# main.net
KiCad netlist of a schematic drawn in Altium Designer
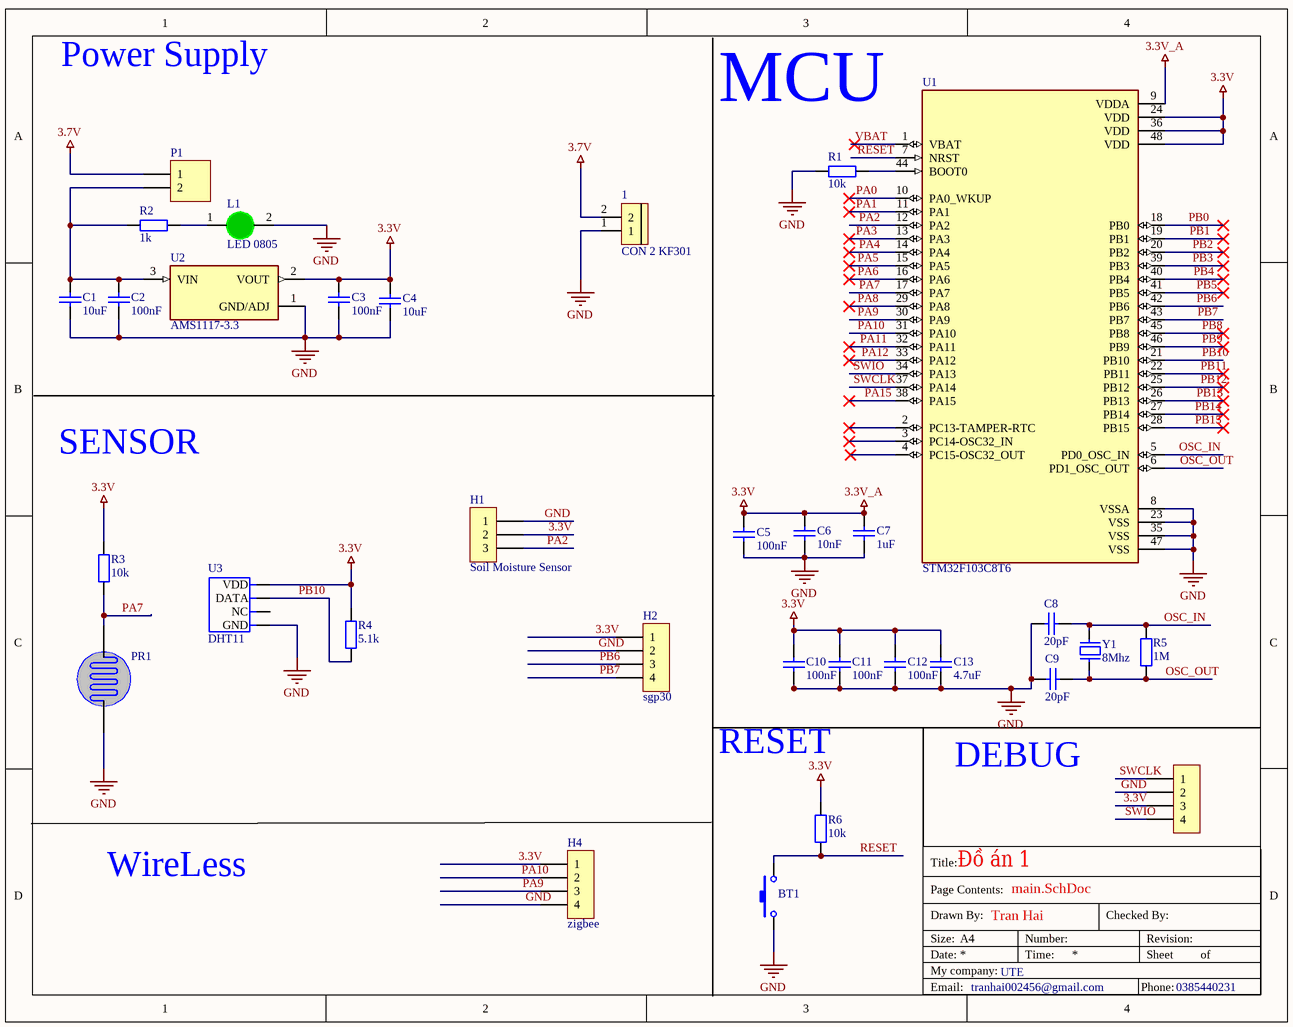
[diagram p0: main.SchDoc]

(export (version "E")
  (design (tool "Eeschema 10.0.6"))
  (components
    (comp (ref "1")
      (value "CON 2 KF301")
      (footprint "Con 2 KF301 5.08")
      (description "Cắm")
      (libsource (lib "Altium_Lib_by_KhueNguyenCreator") (part "CON 2 KF301"))
    )
    (comp (ref "BT1")
      (value "Nut Nhan 2 Chan SMD 3x6x2.5")
      (footprint "Nut Nhan 2 Chan SMD 3x6x2.5")
      (libsource (lib "Altium_Lib_by_KhueNguyenCreator") (part "Nut Nhan 2 Chan SMD 3x6x2.5"))
    )
    (comp (ref "C1")
      (value "10uF")
      (footprint "Tu 0805")
      (description "Dán")
      (libsource (lib "Altium_Lib_by_KhueNguyenCreator") (part "Tu 0805 200pF 50V 10%"))
    )
    (comp (ref "C2")
      (value "100nF")
      (footprint "Tu 0805")
      (description "Dán")
      (libsource (lib "Altium_Lib_by_KhueNguyenCreator") (part "Tu 0805 200pF 50V 10%"))
    )
    (comp (ref "C3")
      (value "100nF")
      (footprint "Tu 0805")
      (description "Dán")
      (libsource (lib "Altium_Lib_by_KhueNguyenCreator") (part "Tu 0805 200pF 50V 10%"))
    )
    (comp (ref "C4")
      (value "10uF")
      (footprint "Tu 0805")
      (description "Dán")
      (libsource (lib "Altium_Lib_by_KhueNguyenCreator") (part "Tu 0805 200pF 50V 10%"))
    )
    (comp (ref "C5")
      (value "100nF")
      (footprint "tu 0805")
      (description "Dán")
      (libsource (lib "") (part "Tu 0805 101 50V 20%_1"))
    )
    (comp (ref "C6")
      (value "10nF")
      (footprint "tu 0805")
      (description "Dán")
      (libsource (lib "") (part "Tu 0805 101 50V 20%_1"))
    )
    (comp (ref "C7")
      (value "1uF")
      (footprint "tu 0805")
      (description "Dán")
      (libsource (lib "") (part "Tu 0805 101 50V 20%_1"))
    )
    (comp (ref "C8")
      (value "20pF")
      (footprint "tu 0805")
      (description "Dán")
      (libsource (lib "") (part "Tu 0805 101 50V 20%_1"))
    )
    (comp (ref "C9")
      (value "20pF")
      (footprint "tu 0805")
      (description "Dán")
      (libsource (lib "") (part "Tu 0805 101 50V 20%_1"))
    )
    (comp (ref "C10")
      (value "100nF")
      (footprint "tu 0805")
      (description "Dán")
      (libsource (lib "Altium_Lib_by_KhueNguyenCreator") (part "Tu 0805 101 50V 20%"))
    )
    (comp (ref "C11")
      (value "100nF")
      (footprint "tu 0805")
      (description "Dán")
      (libsource (lib "Altium_Lib_by_KhueNguyenCreator") (part "Tu 0805 101 50V 20%"))
    )
    (comp (ref "C12")
      (value "100nF")
      (footprint "tu 0805")
      (description "Dán")
      (libsource (lib "Altium_Lib_by_KhueNguyenCreator") (part "Tu 0805 101 50V 20%"))
    )
    (comp (ref "C13")
      (value "4.7uF")
      (footprint "tu 0805")
      (description "Dán")
      (libsource (lib "Altium_Lib_by_KhueNguyenCreator") (part "Tu 0805 101 50V 20%"))
    )
    (comp (ref "H1")
      (value "Soil Moisture Sensor")
      (footprint "XH2.54M-3")
      (description "Cắm")
      (libsource (lib "Altium_Lib_by_KhueNguyenCreator") (part "Header 3P 2.54 Duc Thang"))
    )
    (comp (ref "H2")
      (value "sgp30")
      (footprint "XH2.54M-4")
      (description "Cắm")
      (libsource (lib "Altium_Lib_by_KhueNguyenCreator") (part "Header 4P 2.54 Duc Thang"))
    )
    (comp (ref "H3")
      (value "Header 4P 2.54 Duc Thang")
      (footprint "XH2.54M-4")
      (description "Cắm")
      (libsource (lib "Altium_Lib_by_KhueNguyenCreator") (part "Header 4P 2.54 Duc Thang"))
    )
    (comp (ref "H4")
      (value "zigbee")
      (footprint "XH2.54M-4")
      (description "Cắm")
      (libsource (lib "Altium_Lib_by_KhueNguyenCreator") (part "Header 4P 2.54 Duc Thang"))
    )
    (comp (ref "L1")
      (value "LED 0805")
      (footprint "LED-0805-Green")
      (description "Dán")
      (libsource (lib "Altium_Lib_by_KhueNguyenCreator") (part "LED 0805 Xanh La"))
    )
    (comp (ref "P1")
      (value "Header 2")
      (footprint "HDR1X2")
      (description "Header, 2-Pin")
      (fields (field (name "PUBLISHER") "Altium Limited"))
      (libsource (lib "Library AL") (part "Header 2"))
    )
    (comp (ref "PR1")
      (value "Quang Tro")
      (footprint "Quang Tro")
      (description "Photoresistor")
      (fields (field (name "CREATOR") "Bien Nguyen"))
      (libsource (lib "Altium_Lib_by_KhueNguyenCreator") (part "Quang Tro"))
    )
    (comp (ref "R1")
      (value "10k")
      (footprint "tro smd 0805")
      (description "Dán")
      (libsource (lib "Altium_Lib_by_KhueNguyenCreator") (part "Tro 0805 1% 10k"))
    )
    (comp (ref "R2")
      (value "1k")
      (footprint "tro smd 0805")
      (description "Dán")
      (libsource (lib "Altium_Lib_by_KhueNguyenCreator") (part "Tro 0805 1% 10k"))
    )
    (comp (ref "R3")
      (value "10k")
      (footprint "tro smd 0805")
      (description "Dán")
      (libsource (lib "Altium_Lib_by_KhueNguyenCreator") (part "Tro 0805 1% 10k"))
    )
    (comp (ref "R4")
      (value "5.1k")
      (footprint "tro smd 0805")
      (description "Dán")
      (libsource (lib "Altium_Lib_by_KhueNguyenCreator") (part "Tro 0805 1% 10k"))
    )
    (comp (ref "R5")
      (value "1M")
      (footprint "tro smd 0805")
      (description "Dán")
      (libsource (lib "Altium_Lib_by_KhueNguyenCreator") (part "Tro 0805 1% 10k"))
    )
    (comp (ref "R6")
      (value "10k")
      (footprint "tro smd 0805")
      (description "Dán")
      (libsource (lib "Altium_Lib_by_KhueNguyenCreator") (part "Tro 0805 1% 10k"))
    )
    (comp (ref "U1")
      (value "STM32F103C8T6")
      (footprint "QFP50P900X900X160-48N")
      (description "ARM® Cortex®-M3 STM32F1 Microcontroller IC 32-Bit 72MHz 64KB (64K x 8) FLASH 48-LQFP (7x7)")
      (fields (field (name "MF") "STMicroelectronics"))
      (libsource (lib "STM32F103C8T6") (part "STM32F103C8T6"))
    )
    (comp (ref "U2")
      (value "AMS1117-3.3")
      (footprint "SOT229P700X180-4N")
      (description "Sot223/Pkg 1-Amp 3.3-Volt Low Drop Out Voltage Regulatator")
      (fields (field (name "MF") "Advanced Monolithic Systems"))
      (libsource (lib "AMS1117-3.3") (part "AMS1117-3.3"))
    )
    (comp (ref "U3")
      (value "DHT11")
      (footprint "SNR4-2.54-15.5X12.0X5.5MM")
      (description "Äá»™ áº©m, nhiá»‡t Ä‘á»™ Ká»¹ thuáº­t sá»‘ Â±5% RH qua lá»—")
      (fields (field (name "MF") "UNIVERSAL-SOLDER Electronics Ltd"))
      (libsource (lib "TEM-HUM-DHT11_4P-15.5X12.0MM_") (part "TEM-HUM-DHT11(4P-15.5X12.0MM)"))
    )
    (comp (ref "Y1")
      (value "8Mhz")
      (footprint "Thach Anh 2 chan cam")
      (description "Crystal For all Crystal 2pin.")
      (libsource (lib "Altium_Lib_by_KhueNguyenCreator") (part "Thach Anh 2 chan Cam"))
    )
  )
  (nets
    (net (code "1") (name "/OSC_IN") (class "Default")
      (node (ref "C8") (pin "1") (pinfunction "1_1") (pintype "passive"))
      (node (ref "R5") (pin "2") (pinfunction "2_2") (pintype "passive"))
      (node (ref "U1") (pin "5") (pinfunction "PD0_OSC_IN_5") (pintype "bidirectional"))
      (node (ref "Y1") (pin "2") (pinfunction "2_2") (pintype "passive"))
    )
    (net (code "2") (name "/OSC_OUT") (class "Default")
      (node (ref "C9") (pin "1") (pinfunction "1_1") (pintype "passive"))
      (node (ref "R5") (pin "1") (pinfunction "1_1") (pintype "passive"))
      (node (ref "U1") (pin "6") (pinfunction "PD1_OSC_OUT_6") (pintype "bidirectional"))
      (node (ref "Y1") (pin "1") (pinfunction "1_1") (pintype "passive"))
    )
    (net (code "3") (name "/PA0") (class "Default")
      (node (ref "U1") (pin "10") (pinfunction "PA0_WKUP_10") (pintype "bidirectional+no_connect"))
    )
    (net (code "4") (name "/PA1") (class "Default")
      (node (ref "U1") (pin "11") (pinfunction "PA1_11") (pintype "bidirectional+no_connect"))
    )
    (net (code "5") (name "/PA2") (class "Default")
      (node (ref "H1") (pin "3") (pinfunction "3_3") (pintype "passive"))
      (node (ref "U1") (pin "12") (pinfunction "PA2_12") (pintype "bidirectional"))
    )
    (net (code "6") (name "/PA3") (class "Default")
      (node (ref "U1") (pin "13") (pinfunction "PA3_13") (pintype "bidirectional+no_connect"))
    )
    (net (code "7") (name "/PA4") (class "Default")
      (node (ref "U1") (pin "14") (pinfunction "PA4_14") (pintype "bidirectional+no_connect"))
    )
    (net (code "8") (name "/PA5") (class "Default")
      (node (ref "U1") (pin "15") (pinfunction "PA5_15") (pintype "bidirectional+no_connect"))
    )
    (net (code "9") (name "/PA6") (class "Default")
      (node (ref "U1") (pin "16") (pinfunction "PA6_16") (pintype "bidirectional+no_connect"))
    )
    (net (code "10") (name "/PA7") (class "Default")
      (node (ref "PR1") (pin "1") (pinfunction "1_1") (pintype "passive"))
      (node (ref "R3") (pin "1") (pinfunction "1_1") (pintype "passive"))
      (node (ref "U1") (pin "17") (pinfunction "PA7_17") (pintype "bidirectional"))
    )
    (net (code "11") (name "/PA8") (class "Default")
      (node (ref "U1") (pin "29") (pinfunction "PA8_29") (pintype "bidirectional+no_connect"))
    )
    (net (code "12") (name "/PA9") (class "Default")
      (node (ref "H4") (pin "3") (pinfunction "3_3") (pintype "passive"))
      (node (ref "U1") (pin "30") (pinfunction "PA9_30") (pintype "bidirectional"))
    )
    (net (code "13") (name "/PA10") (class "Default")
      (node (ref "H4") (pin "2") (pinfunction "2_2") (pintype "passive"))
      (node (ref "U1") (pin "31") (pinfunction "PA10_31") (pintype "bidirectional"))
    )
    (net (code "14") (name "/PA11") (class "Default")
      (node (ref "U1") (pin "32") (pinfunction "PA11_32") (pintype "bidirectional+no_connect"))
    )
    (net (code "15") (name "/PA12") (class "Default")
      (node (ref "U1") (pin "33") (pinfunction "PA12_33") (pintype "bidirectional+no_connect"))
    )
    (net (code "16") (name "/PA15") (class "Default")
      (node (ref "U1") (pin "38") (pinfunction "PA15_38") (pintype "bidirectional+no_connect"))
    )
    (net (code "17") (name "/PB0") (class "Default")
      (node (ref "U1") (pin "18") (pinfunction "PB0_18") (pintype "bidirectional+no_connect"))
    )
    (net (code "18") (name "/PB1") (class "Default")
      (node (ref "U1") (pin "19") (pinfunction "PB1_19") (pintype "bidirectional+no_connect"))
    )
    (net (code "19") (name "/PB2") (class "Default")
      (node (ref "U1") (pin "20") (pinfunction "PB2_20") (pintype "bidirectional+no_connect"))
    )
    (net (code "20") (name "/PB3") (class "Default")
      (node (ref "U1") (pin "39") (pinfunction "PB3_39") (pintype "bidirectional+no_connect"))
    )
    (net (code "21") (name "/PB4") (class "Default")
      (node (ref "U1") (pin "40") (pinfunction "PB4_40") (pintype "bidirectional+no_connect"))
    )
    (net (code "22") (name "/PB5") (class "Default")
      (node (ref "U1") (pin "41") (pinfunction "PB5_41") (pintype "bidirectional+no_connect"))
    )
    (net (code "23") (name "/PB6") (class "Default")
      (node (ref "H2") (pin "3") (pinfunction "3_3") (pintype "passive"))
      (node (ref "U1") (pin "42") (pinfunction "PB6_42") (pintype "bidirectional"))
    )
    (net (code "24") (name "/PB7") (class "Default")
      (node (ref "H2") (pin "4") (pinfunction "4_4") (pintype "passive"))
      (node (ref "U1") (pin "43") (pinfunction "PB7_43") (pintype "bidirectional"))
    )
    (net (code "25") (name "/PB8") (class "Default")
      (node (ref "U1") (pin "45") (pinfunction "PB8_45") (pintype "bidirectional+no_connect"))
    )
    (net (code "26") (name "/PB9") (class "Default")
      (node (ref "U1") (pin "46") (pinfunction "PB9_46") (pintype "bidirectional+no_connect"))
    )
    (net (code "27") (name "/PB10") (class "Default")
      (node (ref "R4") (pin "1") (pinfunction "1_1") (pintype "passive"))
      (node (ref "U1") (pin "21") (pinfunction "PB10_21") (pintype "bidirectional"))
      (node (ref "U3") (pin "2") (pinfunction "DATA_2") (pintype "bidirectional"))
    )
    (net (code "28") (name "/PB11") (class "Default")
      (node (ref "U1") (pin "22") (pinfunction "PB11_22") (pintype "bidirectional+no_connect"))
    )
    (net (code "29") (name "/PB12") (class "Default")
      (node (ref "U1") (pin "25") (pinfunction "PB12_25") (pintype "bidirectional+no_connect"))
    )
    (net (code "30") (name "/PB13") (class "Default")
      (node (ref "U1") (pin "26") (pinfunction "PB13_26") (pintype "bidirectional+no_connect"))
    )
    (net (code "31") (name "/PB14") (class "Default")
      (node (ref "U1") (pin "27") (pinfunction "PB14_27") (pintype "bidirectional+no_connect"))
    )
    (net (code "32") (name "/PB15") (class "Default")
      (node (ref "U1") (pin "28") (pinfunction "PB15_28") (pintype "bidirectional+no_connect"))
    )
    (net (code "33") (name "/RESET") (class "Default")
      (node (ref "BT1") (pin "2") (pinfunction "2_2") (pintype "passive"))
      (node (ref "R6") (pin "1") (pinfunction "1_1") (pintype "passive"))
      (node (ref "U1") (pin "7") (pinfunction "NRST_7") (pintype "input"))
    )
    (net (code "34") (name "/SWCLK") (class "Default")
      (node (ref "H3") (pin "1") (pinfunction "1_1") (pintype "passive"))
      (node (ref "U1") (pin "37") (pinfunction "PA14_37") (pintype "bidirectional"))
    )
    (net (code "35") (name "/SWIO") (class "Default")
      (node (ref "H3") (pin "4") (pinfunction "4_4") (pintype "passive"))
      (node (ref "U1") (pin "34") (pinfunction "PA13_34") (pintype "bidirectional"))
    )
    (net (code "37") (name "/VBAT") (class "Default")
      (node (ref "U1") (pin "1") (pinfunction "VBAT_1") (pintype "bidirectional"))
    )
    (net (code "38") (name "3.3V") (class "Default")
      (node (ref "C10") (pin "1") (pinfunction "1_1") (pintype "passive"))
      (node (ref "C11") (pin "1") (pinfunction "1_1") (pintype "passive"))
      (node (ref "C12") (pin "1") (pinfunction "1_1") (pintype "passive"))
      (node (ref "C13") (pin "1") (pinfunction "1_1") (pintype "passive"))
      (node (ref "C3") (pin "1") (pinfunction "1_1") (pintype "passive"))
      (node (ref "C4") (pin "1") (pinfunction "1_1") (pintype "passive"))
      (node (ref "C5") (pin "1") (pinfunction "1_1") (pintype "passive"))
      (node (ref "C6") (pin "1") (pinfunction "1_1") (pintype "passive"))
      (node (ref "C7") (pin "1") (pinfunction "1_1") (pintype "passive"))
      (node (ref "H1") (pin "2") (pinfunction "2_2") (pintype "passive"))
      (node (ref "H2") (pin "1") (pinfunction "1_1") (pintype "passive"))
      (node (ref "H3") (pin "3") (pinfunction "3_3") (pintype "passive"))
      (node (ref "H4") (pin "1") (pinfunction "1_1") (pintype "passive"))
      (node (ref "R3") (pin "2") (pinfunction "2_2") (pintype "passive"))
      (node (ref "R4") (pin "2") (pinfunction "2_2") (pintype "passive"))
      (node (ref "R6") (pin "2") (pinfunction "2_2") (pintype "passive"))
      (node (ref "U1") (pin "24") (pinfunction "VDD_24") (pintype "power_in"))
      (node (ref "U1") (pin "36") (pinfunction "VDD_36") (pintype "power_in"))
      (node (ref "U1") (pin "48") (pinfunction "VDD_48") (pintype "power_in"))
      (node (ref "U1") (pin "9") (pinfunction "VDDA_9") (pintype "power_in"))
      (node (ref "U2") (pin "2") (pinfunction "VOUT_2") (pintype "output"))
      (node (ref "U3") (pin "1") (pinfunction "VDD_1") (pintype "power_in"))
    )
    (net (code "39") (name "3.7V") (class "Default")
      (node (ref "1") (pin "2") (pinfunction "2_2") (pintype "passive"))
      (node (ref "P1") (pin "1") (pinfunction "1_1") (pintype "passive"))
    )
    (net (code "40") (name "GND") (class "Default")
      (node (ref "1") (pin "1") (pinfunction "1_1") (pintype "passive"))
      (node (ref "BT1") (pin "1") (pinfunction "1_1") (pintype "passive"))
      (node (ref "C1") (pin "2") (pinfunction "2_2") (pintype "passive"))
      (node (ref "C10") (pin "2") (pinfunction "2_2") (pintype "passive"))
      (node (ref "C11") (pin "2") (pinfunction "2_2") (pintype "passive"))
      (node (ref "C12") (pin "2") (pinfunction "2_2") (pintype "passive"))
      (node (ref "C13") (pin "2") (pinfunction "2_2") (pintype "passive"))
      (node (ref "C2") (pin "2") (pinfunction "2_2") (pintype "passive"))
      (node (ref "C3") (pin "2") (pinfunction "2_2") (pintype "passive"))
      (node (ref "C4") (pin "2") (pinfunction "2_2") (pintype "passive"))
      (node (ref "C5") (pin "2") (pinfunction "2_2") (pintype "passive"))
      (node (ref "C6") (pin "2") (pinfunction "2_2") (pintype "passive"))
      (node (ref "C7") (pin "2") (pinfunction "2_2") (pintype "passive"))
      (node (ref "C8") (pin "2") (pinfunction "2_2") (pintype "passive"))
      (node (ref "C9") (pin "2") (pinfunction "2_2") (pintype "passive"))
      (node (ref "H1") (pin "1") (pinfunction "1_1") (pintype "passive"))
      (node (ref "H2") (pin "2") (pinfunction "2_2") (pintype "passive"))
      (node (ref "H3") (pin "2") (pinfunction "2_2") (pintype "passive"))
      (node (ref "H4") (pin "4") (pinfunction "4_4") (pintype "passive"))
      (node (ref "L1") (pin "2") (pinfunction "K_2") (pintype "passive"))
      (node (ref "PR1") (pin "2") (pinfunction "2_2") (pintype "passive"))
      (node (ref "R1") (pin "1") (pinfunction "1_1") (pintype "passive"))
      (node (ref "U1") (pin "23") (pinfunction "VSS_23") (pintype "power_in"))
      (node (ref "U1") (pin "35") (pinfunction "VSS_35") (pintype "power_in"))
      (node (ref "U1") (pin "47") (pinfunction "VSS_47") (pintype "power_in"))
      (node (ref "U1") (pin "8") (pinfunction "VSSA_8") (pintype "power_in"))
      (node (ref "U2") (pin "1") (pinfunction "GND/ADJ_1") (pintype "power_in"))
      (node (ref "U3") (pin "4") (pinfunction "GND_4") (pintype "power_in"))
    )
    (net (code "41") (name "Net-(L1-A)") (class "Default")
      (node (ref "L1") (pin "1") (pinfunction "A_1") (pintype "passive"))
      (node (ref "R2") (pin "2") (pinfunction "2_2") (pintype "passive"))
    )
    (net (code "42") (name "Net-(U1-BOOT0)") (class "Default")
      (node (ref "R1") (pin "2") (pinfunction "2_2") (pintype "passive"))
      (node (ref "U1") (pin "44") (pinfunction "BOOT0_44") (pintype "input"))
    )
    (net (code "43") (name "Net-(U2-VIN)") (class "Default")
      (node (ref "C1") (pin "1") (pinfunction "1_1") (pintype "passive"))
      (node (ref "C2") (pin "1") (pinfunction "1_1") (pintype "passive"))
      (node (ref "P1") (pin "2") (pinfunction "2_2") (pintype "passive"))
      (node (ref "R2") (pin "1") (pinfunction "1_1") (pintype "passive"))
      (node (ref "U2") (pin "3") (pinfunction "VIN_3") (pintype "input"))
    )
    (net (code "44") (name "unconnected-(U1-PC13-TAMPER-RTC-Pad2)") (class "Default")
      (node (ref "U1") (pin "2") (pinfunction "PC13-TAMPER-RTC_2") (pintype "bidirectional+no_connect"))
    )
    (net (code "45") (name "unconnected-(U1-PC14-OSC32_IN-Pad3)") (class "Default")
      (node (ref "U1") (pin "3") (pinfunction "PC14-OSC32_IN_3") (pintype "bidirectional+no_connect"))
    )
    (net (code "46") (name "unconnected-(U1-PC15-OSC32_OUT-Pad4)") (class "Default")
      (node (ref "U1") (pin "4") (pinfunction "PC15-OSC32_OUT_4") (pintype "bidirectional+no_connect"))
    )
    (net (code "47") (name "unconnected-(U3-NC-Pad3)") (class "Default")
      (node (ref "U3") (pin "3") (pinfunction "NC_3") (pintype "passive"))
    )
  )
)
